# cando.net
KiCad netlist of a schematic drawn in Altium Designer
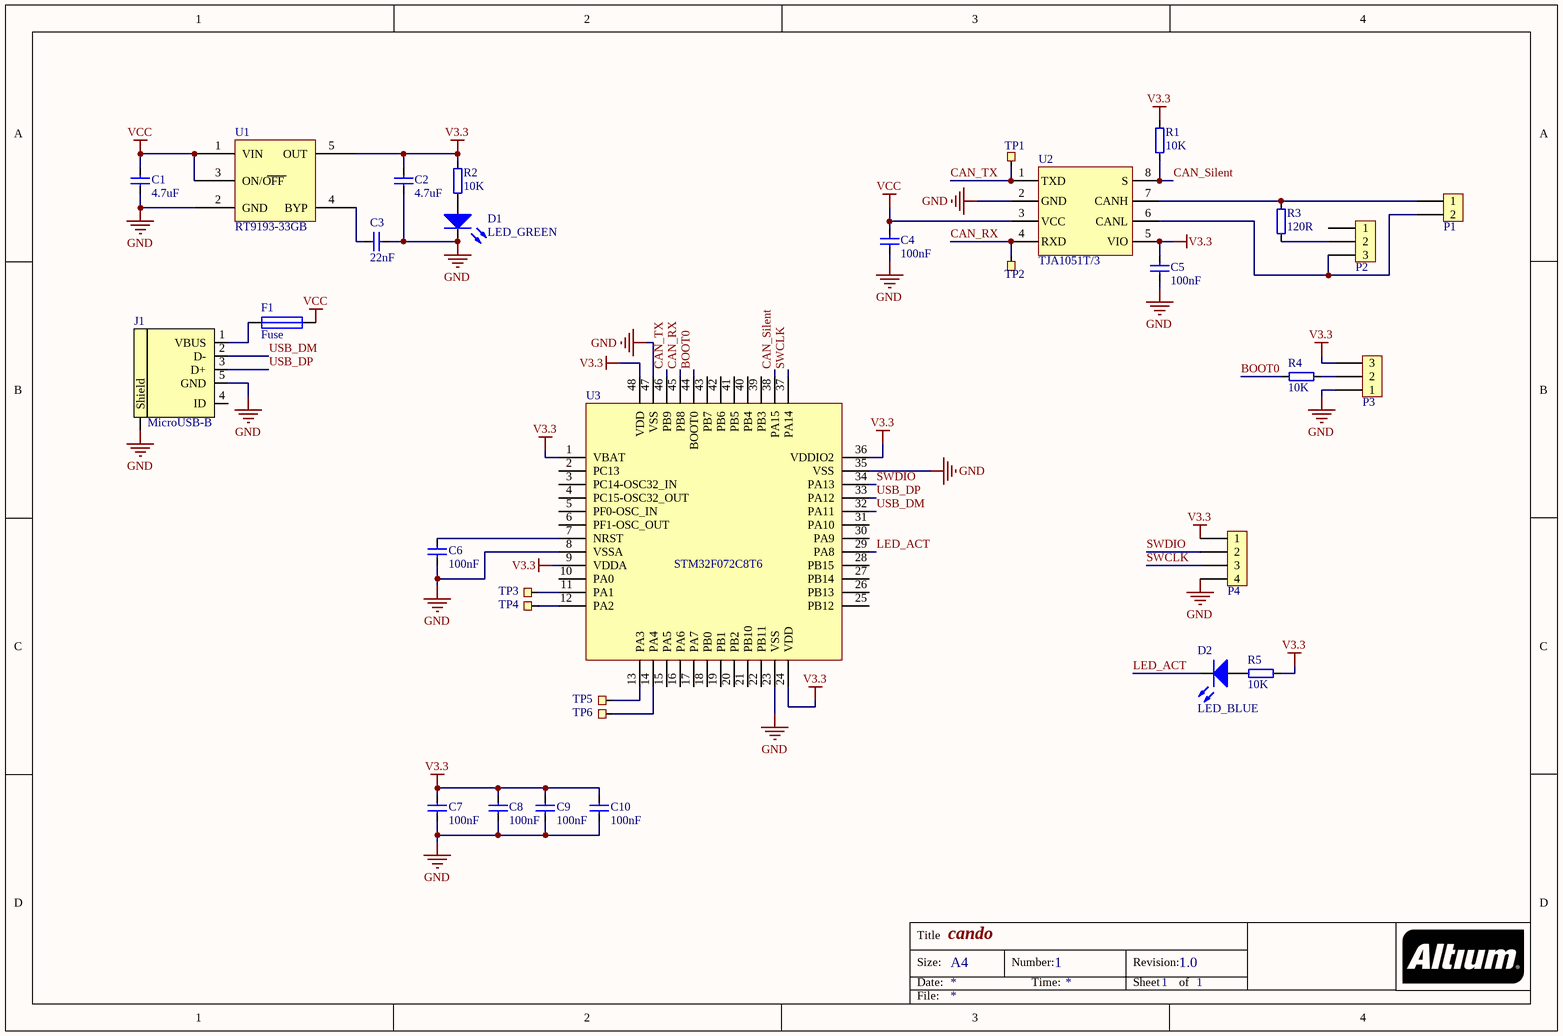
[diagram p0: cando.SchDoc]

(export (version "E")
  (design (tool "Eeschema 10.0.6"))
  (components
    (comp (ref "C1")
      (value "4.7uF")
      (footprint "0603C")
      (description "Capacitor")
      (libsource (lib "SCH_LIB") (part "CAP"))
    )
    (comp (ref "C2")
      (value "4.7uF")
      (footprint "0603C")
      (description "Capacitor")
      (libsource (lib "SCH_LIB") (part "CAP"))
    )
    (comp (ref "C3")
      (value "22nF")
      (footprint "0603C")
      (description "Capacitor")
      (libsource (lib "SCH_LIB") (part "CAP"))
    )
    (comp (ref "C4")
      (value "100nF")
      (footprint "0603C")
      (description "Capacitor")
      (libsource (lib "SCH_LIB") (part "CAP"))
    )
    (comp (ref "C5")
      (value "100nF")
      (footprint "0603C")
      (description "Capacitor")
      (libsource (lib "SCH_LIB") (part "CAP"))
    )
    (comp (ref "C6")
      (value "100nF")
      (footprint "0603C")
      (description "Capacitor")
      (libsource (lib "SCH_LIB") (part "CAP"))
    )
    (comp (ref "C7")
      (value "100nF")
      (footprint "0603C")
      (description "Capacitor")
      (libsource (lib "SCH_LIB") (part "CAP"))
    )
    (comp (ref "C8")
      (value "100nF")
      (footprint "0603C")
      (description "Capacitor")
      (libsource (lib "SCH_LIB") (part "CAP"))
    )
    (comp (ref "C9")
      (value "100nF")
      (footprint "0603C")
      (description "Capacitor")
      (libsource (lib "SCH_LIB") (part "CAP"))
    )
    (comp (ref "C10")
      (value "100nF")
      (footprint "0603C")
      (description "Capacitor")
      (libsource (lib "SCH_LIB") (part "CAP"))
    )
    (comp (ref "D1")
      (value "LED_GREEN")
      (footprint "LED_0603_GREEN")
      (description "LED")
      (libsource (lib "SCH_LIB") (part "LED"))
    )
    (comp (ref "D2")
      (value "LED_BLUE")
      (footprint "LED_0603_BLUE")
      (description "LED")
      (libsource (lib "SCH_LIB") (part "LED"))
    )
    (comp (ref "F1") (value "Fuse") (footprint "FUSE_0805") (libsource (lib "SCH_LIB") (part "Fuse")))
    (comp (ref "J1")
      (value "MicroUSB-B")
      (footprint "USB-Micro_0")
      (description "MicroUSB-B-SMT")
      (libsource (lib "SCH_LIB") (part "MiniUSB-AB-SMT"))
    )
    (comp (ref "P1")
      (value "MKDSN1.5_2-5.08")
      (footprint "MKDSN-5.08-3P")
      (description "Header_2_2.54")
      (libsource (lib "SCH_LIB") (part "Header_2"))
    )
    (comp (ref "P2") (value "Header_3_2.54") (footprint "HEADER_3") (libsource (lib "") (part "Header_3_1")))
    (comp (ref "P3")
      (value "Header_3_2.54")
      (footprint "HEADER_3")
      (libsource (lib "SCH_LIB") (part "Header_3"))
    )
    (comp (ref "P4")
      (value "PAD_4_2.54")
      (footprint "HEADER_4_PAD")
      (description "Header_4_2.54")
      (libsource (lib "SCH_LIB") (part "Header_4"))
    )
    (comp (ref "R1")
      (value "10K")
      (footprint "0603R")
      (description "Resistor")
      (libsource (lib "SCH_LIB") (part "RES"))
    )
    (comp (ref "R2")
      (value "10K")
      (footprint "0603R")
      (description "Resistor")
      (libsource (lib "SCH_LIB") (part "RES"))
    )
    (comp (ref "R3")
      (value "120R")
      (footprint "0603R")
      (description "Resistor")
      (libsource (lib "SCH_LIB") (part "RES"))
    )
    (comp (ref "R4")
      (value "10K")
      (footprint "0603R")
      (description "Resistor")
      (libsource (lib "SCH_LIB") (part "RES"))
    )
    (comp (ref "R5")
      (value "10K")
      (footprint "0603R")
      (description "Resistor")
      (libsource (lib "SCH_LIB") (part "RES"))
    )
    (comp (ref "TP1")
      (value "Ø1.5mm,SMD")
      (footprint "TP_SMD")
      (description "1.0mm circular SMD testpad")
      (libsource (lib "") (part "TP_SMD_Ø1.0MM_2"))
    )
    (comp (ref "TP2")
      (value "Ø1.5mm,SMD")
      (footprint "TP_SMD")
      (description "1.0mm circular SMD testpad")
      (libsource (lib "") (part "TP_SMD_Ø1.0MM_1"))
    )
    (comp (ref "TP3")
      (value "Ø1.5mm,SMD")
      (footprint "TP_SMD")
      (description "1.0mm circular SMD testpad")
      (libsource (lib "SCH_LIB") (part "TP_SMD_Ø1.0MM"))
    )
    (comp (ref "TP4")
      (value "Ø1.5mm,SMD")
      (footprint "TP_SMD")
      (description "1.0mm circular SMD testpad")
      (libsource (lib "SCH_LIB") (part "TP_SMD_Ø1.0MM"))
    )
    (comp (ref "TP5")
      (value "Ø1.5mm,SMD")
      (footprint "TP_SMD")
      (description "1.0mm circular SMD testpad")
      (libsource (lib "SCH_LIB") (part "TP_SMD_Ø1.0MM"))
    )
    (comp (ref "TP6")
      (value "Ø1.5mm,SMD")
      (footprint "TP_SMD")
      (description "1.0mm circular SMD testpad")
      (libsource (lib "SCH_LIB") (part "TP_SMD_Ø1.0MM"))
    )
    (comp (ref "U1")
      (value "RT9193-33GB")
      (footprint "SOT23-5")
      (description "Chip, RT9193-33GB, LDO Regulator")
      (libsource (lib "SCH_LIB") (part "RT9193-33GB"))
    )
    (comp (ref "U2")
      (value "TJA1051T/3")
      (footprint "SOIC8")
      (description "Chip, TJA1051T/3, CAN chip")
      (libsource (lib "SCH_LIB") (part "TJA1051T/3"))
    )
    (comp (ref "U3")
      (value "STM32F072C8T6")
      (footprint "STM-LQFP48_N")
      (libsource (lib "SCH_LIB") (part "STM32F072C8T6"))
    )
  )
  (nets
    (net (code "1") (name "/BOOT0") (class "Default")
      (node (ref "R4") (pin "1") (pinfunction "1_1") (pintype "passive"))
      (node (ref "U3") (pin "44") (pinfunction "BOOT0_44") (pintype "passive"))
    )
    (net (code "2") (name "/CAN_RX") (class "Default")
      (node (ref "TP2") (pin "1") (pinfunction "1_1") (pintype "passive"))
      (node (ref "U2") (pin "4") (pinfunction "RXD_4") (pintype "passive"))
      (node (ref "U3") (pin "45") (pinfunction "PB8_45") (pintype "passive"))
    )
    (net (code "3") (name "/CAN_Silent") (class "Default")
      (node (ref "R1") (pin "1") (pinfunction "1_1") (pintype "passive"))
      (node (ref "U2") (pin "8") (pinfunction "S_8") (pintype "passive"))
      (node (ref "U3") (pin "38") (pinfunction "PA15_38") (pintype "passive"))
    )
    (net (code "4") (name "/CAN_TX") (class "Default")
      (node (ref "TP1") (pin "1") (pinfunction "1_1") (pintype "passive"))
      (node (ref "U2") (pin "1") (pinfunction "TXD_1") (pintype "passive"))
      (node (ref "U3") (pin "46") (pinfunction "PB9_46") (pintype "passive"))
    )
    (net (code "5") (name "/LED_ACT") (class "Default")
      (node (ref "D2") (pin "2") (pinfunction "K_2") (pintype "passive"))
      (node (ref "U3") (pin "29") (pinfunction "PA8_29") (pintype "passive"))
    )
    (net (code "6") (name "/SWCLK") (class "Default")
      (node (ref "P4") (pin "3") (pinfunction "3_3") (pintype "passive"))
      (node (ref "U3") (pin "37") (pinfunction "PA14_37") (pintype "passive"))
    )
    (net (code "7") (name "/SWDIO") (class "Default")
      (node (ref "P4") (pin "2") (pinfunction "2_2") (pintype "passive"))
      (node (ref "U3") (pin "34") (pinfunction "PA13_34") (pintype "passive"))
    )
    (net (code "8") (name "/USB_DM") (class "Default")
      (node (ref "J1") (pin "2") (pinfunction "D-_2") (pintype "passive"))
      (node (ref "U3") (pin "32") (pinfunction "PA11_32") (pintype "passive"))
    )
    (net (code "9") (name "/USB_DP") (class "Default")
      (node (ref "J1") (pin "3") (pinfunction "D+_3") (pintype "passive"))
      (node (ref "U3") (pin "33") (pinfunction "PA12_33") (pintype "passive"))
    )
    (net (code "10") (name "GND") (class "Default")
      (node (ref "C1") (pin "2") (pinfunction "2_2") (pintype "passive"))
      (node (ref "C10") (pin "2") (pinfunction "2_2") (pintype "passive"))
      (node (ref "C2") (pin "2") (pinfunction "2_2") (pintype "passive"))
      (node (ref "C3") (pin "2") (pinfunction "2_2") (pintype "passive"))
      (node (ref "C4") (pin "2") (pinfunction "2_2") (pintype "passive"))
      (node (ref "C5") (pin "2") (pinfunction "2_2") (pintype "passive"))
      (node (ref "C6") (pin "2") (pinfunction "2_2") (pintype "passive"))
      (node (ref "C7") (pin "2") (pinfunction "2_2") (pintype "passive"))
      (node (ref "C8") (pin "2") (pinfunction "2_2") (pintype "passive"))
      (node (ref "C9") (pin "2") (pinfunction "2_2") (pintype "passive"))
      (node (ref "D1") (pin "2") (pinfunction "K_2") (pintype "passive"))
      (node (ref "J1") (pin "5") (pinfunction "GND_5") (pintype "power_in"))
      (node (ref "J1") (pin "6") (pinfunction "Shield_6") (pintype "power_in"))
      (node (ref "P3") (pin "1") (pinfunction "1_1") (pintype "passive"))
      (node (ref "P4") (pin "4") (pinfunction "4_4") (pintype "passive"))
      (node (ref "U1") (pin "2") (pinfunction "GND_2") (pintype "passive"))
      (node (ref "U2") (pin "2") (pinfunction "GND_2") (pintype "passive"))
      (node (ref "U3") (pin "23") (pinfunction "VSS_23") (pintype "passive"))
      (node (ref "U3") (pin "35") (pinfunction "VSS_35") (pintype "passive"))
      (node (ref "U3") (pin "47") (pinfunction "VSS_47") (pintype "passive"))
      (node (ref "U3") (pin "8") (pinfunction "VSSA_8") (pintype "passive"))
    )
    (net (code "11") (name "Net-(D1-A)") (class "Default")
      (node (ref "D1") (pin "1") (pinfunction "A_1") (pintype "passive"))
      (node (ref "R2") (pin "2") (pinfunction "2_2") (pintype "passive"))
    )
    (net (code "12") (name "Net-(D2-A)") (class "Default")
      (node (ref "D2") (pin "1") (pinfunction "A_1") (pintype "passive"))
      (node (ref "R5") (pin "2") (pinfunction "2_2") (pintype "passive"))
    )
    (net (code "13") (name "Net-(J1-VBUS)") (class "Default")
      (node (ref "F1") (pin "1") (pinfunction "1_1") (pintype "passive"))
      (node (ref "J1") (pin "1") (pinfunction "VBUS_1") (pintype "power_in"))
    )
    (net (code "14") (name "Net-(P2-Pad2)") (class "Default")
      (node (ref "P2") (pin "2") (pinfunction "2_2") (pintype "passive"))
      (node (ref "R3") (pin "2") (pinfunction "2_2") (pintype "passive"))
    )
    (net (code "15") (name "Net-(P3-Pad2)") (class "Default")
      (node (ref "P3") (pin "2") (pinfunction "2_2") (pintype "passive"))
      (node (ref "R4") (pin "2") (pinfunction "2_2") (pintype "passive"))
    )
    (net (code "16") (name "Net-(U1-BYP)") (class "Default")
      (node (ref "C3") (pin "1") (pinfunction "1_1") (pintype "passive"))
      (node (ref "U1") (pin "4") (pinfunction "BYP_4") (pintype "passive"))
    )
    (net (code "17") (name "Net-(U2-CANH)") (class "Default")
      (node (ref "P1") (pin "1") (pinfunction "1_1") (pintype "passive"))
      (node (ref "R3") (pin "1") (pinfunction "1_1") (pintype "passive"))
      (node (ref "U2") (pin "7") (pinfunction "CANH_7") (pintype "passive"))
    )
    (net (code "18") (name "Net-(U2-CANL)") (class "Default")
      (node (ref "P1") (pin "2") (pinfunction "2_2") (pintype "passive"))
      (node (ref "P2") (pin "3") (pinfunction "3_3") (pintype "passive"))
      (node (ref "U2") (pin "6") (pinfunction "CANL_6") (pintype "passive"))
    )
    (net (code "19") (name "Net-(U3-NRST)") (class "Default")
      (node (ref "C6") (pin "1") (pinfunction "1_1") (pintype "passive"))
      (node (ref "U3") (pin "7") (pinfunction "NRST_7") (pintype "passive"))
    )
    (net (code "20") (name "Net-(U3-PA1)") (class "Default")
      (node (ref "TP3") (pin "1") (pinfunction "1_1") (pintype "passive"))
      (node (ref "U3") (pin "11") (pinfunction "PA1_11") (pintype "passive"))
    )
    (net (code "21") (name "Net-(U3-PA2)") (class "Default")
      (node (ref "TP4") (pin "1") (pinfunction "1_1") (pintype "passive"))
      (node (ref "U3") (pin "12") (pinfunction "PA2_12") (pintype "passive"))
    )
    (net (code "22") (name "Net-(U3-PA3)") (class "Default")
      (node (ref "TP5") (pin "1") (pinfunction "1_1") (pintype "passive"))
      (node (ref "U3") (pin "13") (pinfunction "PA3_13") (pintype "passive"))
    )
    (net (code "23") (name "Net-(U3-PA4)") (class "Default")
      (node (ref "TP6") (pin "1") (pinfunction "1_1") (pintype "passive"))
      (node (ref "U3") (pin "14") (pinfunction "PA4_14") (pintype "passive"))
    )
    (net (code "24") (name "V3.3") (class "Default")
      (node (ref "C10") (pin "1") (pinfunction "1_1") (pintype "passive"))
      (node (ref "C2") (pin "1") (pinfunction "1_1") (pintype "passive"))
      (node (ref "C5") (pin "1") (pinfunction "1_1") (pintype "passive"))
      (node (ref "C7") (pin "1") (pinfunction "1_1") (pintype "passive"))
      (node (ref "C8") (pin "1") (pinfunction "1_1") (pintype "passive"))
      (node (ref "C9") (pin "1") (pinfunction "1_1") (pintype "passive"))
      (node (ref "P3") (pin "3") (pinfunction "3_3") (pintype "passive"))
      (node (ref "P4") (pin "1") (pinfunction "1_1") (pintype "passive"))
      (node (ref "R1") (pin "2") (pinfunction "2_2") (pintype "passive"))
      (node (ref "R2") (pin "1") (pinfunction "1_1") (pintype "passive"))
      (node (ref "R5") (pin "1") (pinfunction "1_1") (pintype "passive"))
      (node (ref "U1") (pin "5") (pinfunction "OUT_5") (pintype "passive"))
      (node (ref "U2") (pin "5") (pinfunction "VIO_5") (pintype "passive"))
      (node (ref "U3") (pin "1") (pinfunction "VBAT_1") (pintype "passive"))
      (node (ref "U3") (pin "24") (pinfunction "VDD_24") (pintype "passive"))
      (node (ref "U3") (pin "36") (pinfunction "VDDIO2_36") (pintype "passive"))
      (node (ref "U3") (pin "48") (pinfunction "VDD_48") (pintype "passive"))
      (node (ref "U3") (pin "9") (pinfunction "VDDA_9") (pintype "passive"))
    )
    (net (code "25") (name "VCC") (class "Default")
      (node (ref "C1") (pin "1") (pinfunction "1_1") (pintype "passive"))
      (node (ref "C4") (pin "1") (pinfunction "1_1") (pintype "passive"))
      (node (ref "F1") (pin "2") (pinfunction "2_2") (pintype "passive"))
      (node (ref "U1") (pin "1") (pinfunction "VIN_1") (pintype "passive"))
      (node (ref "U1") (pin "3") (pinfunction "ON/OFF_3") (pintype "passive"))
      (node (ref "U2") (pin "3") (pinfunction "VCC_3") (pintype "passive"))
    )
    (net (code "26") (name "unconnected-(J1-ID-Pad4)") (class "Default")
      (node (ref "J1") (pin "4") (pinfunction "ID_4") (pintype "passive"))
    )
    (net (code "27") (name "unconnected-(P2-Pad1)") (class "Default")
      (node (ref "P2") (pin "1") (pinfunction "1_1") (pintype "passive"))
    )
    (net (code "28") (name "unconnected-(U3-PA0-Pad10)") (class "Default")
      (node (ref "U3") (pin "10") (pinfunction "PA0_10") (pintype "passive"))
    )
    (net (code "29") (name "unconnected-(U3-PA5-Pad15)") (class "Default")
      (node (ref "U3") (pin "15") (pinfunction "PA5_15") (pintype "passive"))
    )
    (net (code "30") (name "unconnected-(U3-PA6-Pad16)") (class "Default")
      (node (ref "U3") (pin "16") (pinfunction "PA6_16") (pintype "passive"))
    )
    (net (code "31") (name "unconnected-(U3-PA7-Pad17)") (class "Default")
      (node (ref "U3") (pin "17") (pinfunction "PA7_17") (pintype "passive"))
    )
    (net (code "32") (name "unconnected-(U3-PA9-Pad30)") (class "Default")
      (node (ref "U3") (pin "30") (pinfunction "PA9_30") (pintype "passive"))
    )
    (net (code "33") (name "unconnected-(U3-PA10-Pad31)") (class "Default")
      (node (ref "U3") (pin "31") (pinfunction "PA10_31") (pintype "passive"))
    )
    (net (code "34") (name "unconnected-(U3-PB0-Pad18)") (class "Default")
      (node (ref "U3") (pin "18") (pinfunction "PB0_18") (pintype "passive"))
    )
    (net (code "35") (name "unconnected-(U3-PB1-Pad19)") (class "Default")
      (node (ref "U3") (pin "19") (pinfunction "PB1_19") (pintype "passive"))
    )
    (net (code "36") (name "unconnected-(U3-PB2-Pad20)") (class "Default")
      (node (ref "U3") (pin "20") (pinfunction "PB2_20") (pintype "passive"))
    )
    (net (code "37") (name "unconnected-(U3-PB3-Pad39)") (class "Default")
      (node (ref "U3") (pin "39") (pinfunction "PB3_39") (pintype "passive"))
    )
    (net (code "38") (name "unconnected-(U3-PB4-Pad40)") (class "Default")
      (node (ref "U3") (pin "40") (pinfunction "PB4_40") (pintype "passive"))
    )
    (net (code "39") (name "unconnected-(U3-PB5-Pad41)") (class "Default")
      (node (ref "U3") (pin "41") (pinfunction "PB5_41") (pintype "passive"))
    )
    (net (code "40") (name "unconnected-(U3-PB6-Pad42)") (class "Default")
      (node (ref "U3") (pin "42") (pinfunction "PB6_42") (pintype "passive"))
    )
    (net (code "41") (name "unconnected-(U3-PB7-Pad43)") (class "Default")
      (node (ref "U3") (pin "43") (pinfunction "PB7_43") (pintype "passive"))
    )
    (net (code "42") (name "unconnected-(U3-PB10-Pad21)") (class "Default")
      (node (ref "U3") (pin "21") (pinfunction "PB10_21") (pintype "passive"))
    )
    (net (code "43") (name "unconnected-(U3-PB11-Pad22)") (class "Default")
      (node (ref "U3") (pin "22") (pinfunction "PB11_22") (pintype "passive"))
    )
    (net (code "44") (name "unconnected-(U3-PB12-Pad25)") (class "Default")
      (node (ref "U3") (pin "25") (pinfunction "PB12_25") (pintype "passive"))
    )
    (net (code "45") (name "unconnected-(U3-PB13-Pad26)") (class "Default")
      (node (ref "U3") (pin "26") (pinfunction "PB13_26") (pintype "passive"))
    )
    (net (code "46") (name "unconnected-(U3-PB14-Pad27)") (class "Default")
      (node (ref "U3") (pin "27") (pinfunction "PB14_27") (pintype "passive"))
    )
    (net (code "47") (name "unconnected-(U3-PB15-Pad28)") (class "Default")
      (node (ref "U3") (pin "28") (pinfunction "PB15_28") (pintype "passive"))
    )
    (net (code "48") (name "unconnected-(U3-PC13-Pad2)") (class "Default")
      (node (ref "U3") (pin "2") (pinfunction "PC13_2") (pintype "passive"))
    )
    (net (code "49") (name "unconnected-(U3-PC14-OSC32_IN-Pad3)") (class "Default")
      (node (ref "U3") (pin "3") (pinfunction "PC14-OSC32_IN_3") (pintype "passive"))
    )
    (net (code "50") (name "unconnected-(U3-PC15-OSC32_OUT-Pad4)") (class "Default")
      (node (ref "U3") (pin "4") (pinfunction "PC15-OSC32_OUT_4") (pintype "passive"))
    )
    (net (code "51") (name "unconnected-(U3-PF0-OSC_IN-Pad5)") (class "Default")
      (node (ref "U3") (pin "5") (pinfunction "PF0-OSC_IN_5") (pintype "passive"))
    )
    (net (code "52") (name "unconnected-(U3-PF1-OSC_OUT-Pad6)") (class "Default")
      (node (ref "U3") (pin "6") (pinfunction "PF1-OSC_OUT_6") (pintype "passive"))
    )
  )
)
